# 15_-MCU_CONNECTORS.net
KiCad netlist of a schematic drawn in Altium Designer
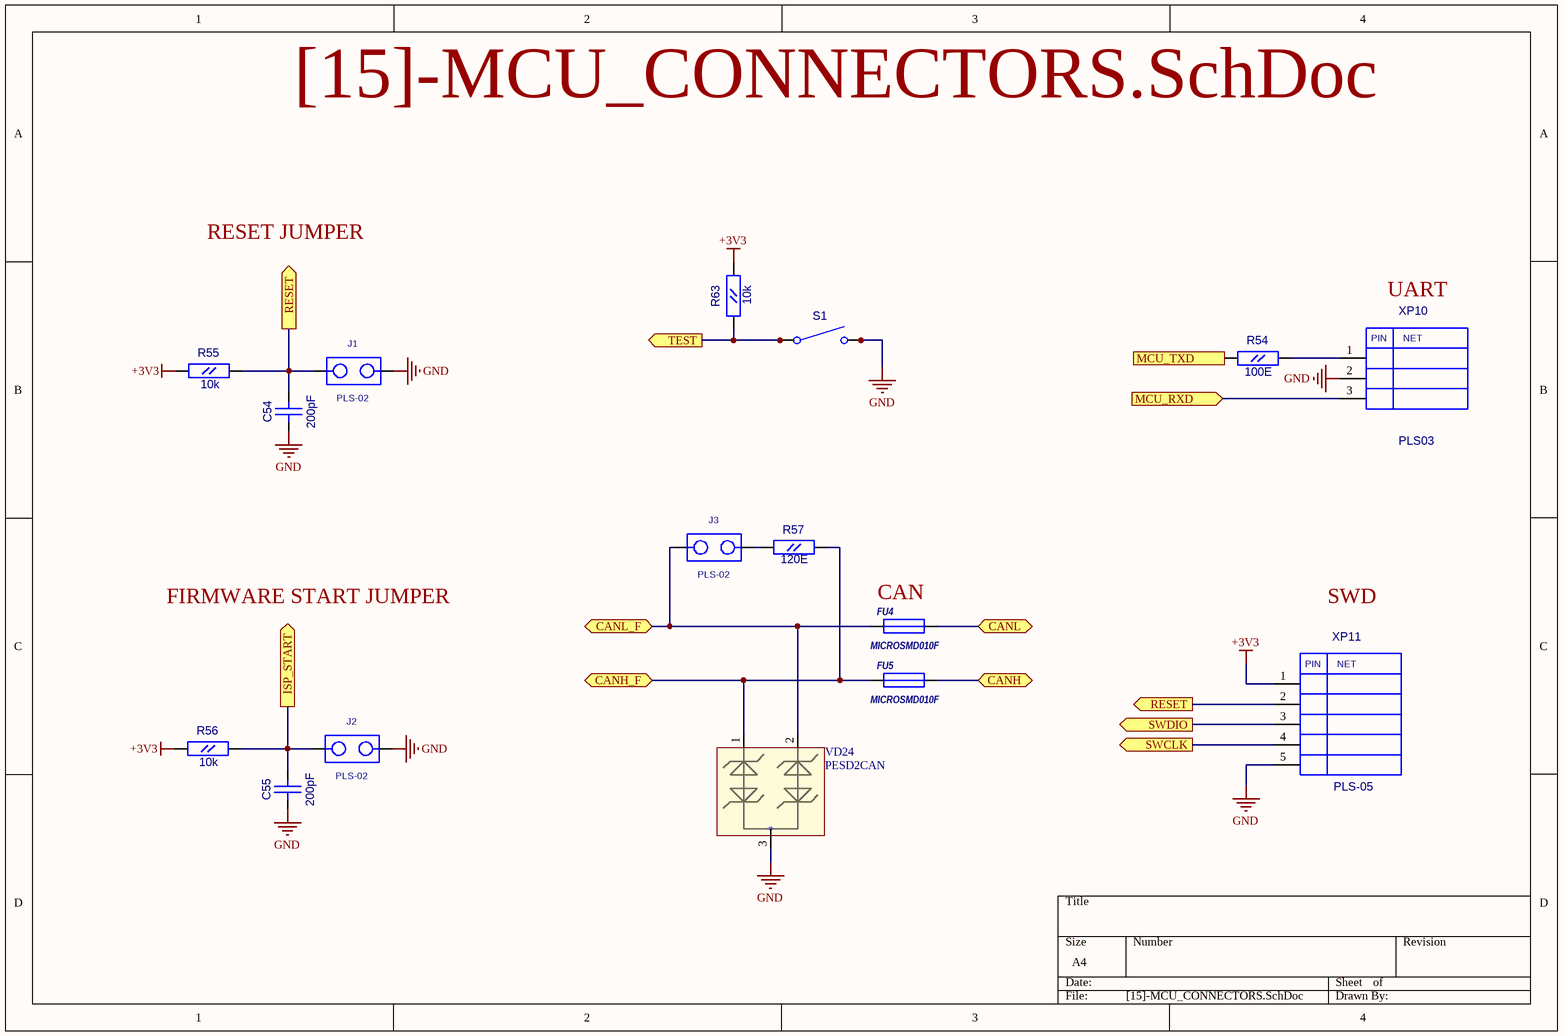
[diagram p0: [15]-MCU_CONNECTORS.SchDoc]

(export (version "E")
  (design (tool "Eeschema 10.0.6"))
  (components
    (comp (ref "C54")
      (value "200pF")
      (footprint "CC0603")
      (description "CC0603")
      (libsource (lib "gprs_modem_2") (part "CC0603"))
    )
    (comp (ref "C55")
      (value "200pF")
      (footprint "CC0603")
      (description "CC0603")
      (libsource (lib "gprs_modem_2") (part "CC0603"))
    )
    (comp (ref "FU4")
      (value "MICROSMD010F")
      (footprint "RC1210")
      (description "MICROSMD")
      (libsource (lib "gprs_modem_2") (part "MICROSMD"))
    )
    (comp (ref "FU5")
      (value "MICROSMD010F")
      (footprint "RC1210")
      (description "MICROSMD")
      (libsource (lib "gprs_modem_2") (part "MICROSMD"))
    )
    (comp (ref "J1") (value "PLS-02") (footprint "PLS-02") (libsource (lib "gprs_modem_2") (part "PLS-02")))
    (comp (ref "J2") (value "PLS-02") (footprint "PLS-02") (libsource (lib "gprs_modem_2") (part "PLS-02")))
    (comp (ref "J3") (value "PLS-02") (footprint "PLS-02") (libsource (lib "fizik_lib") (part "PLS-02")))
    (comp (ref "R54")
      (value "100E")
      (footprint "RC0603")
      (description "RC0603")
      (libsource (lib "gprs_modem_2") (part "RC0603"))
    )
    (comp (ref "R55")
      (value "10k")
      (footprint "RC0603")
      (description "RC0603")
      (libsource (lib "gprs_modem_2") (part "RC0603"))
    )
    (comp (ref "R56")
      (value "10k")
      (footprint "RC0603")
      (description "RC0603")
      (libsource (lib "gprs_modem_2") (part "RC0603"))
    )
    (comp (ref "R57")
      (value "120E")
      (footprint "RC0805")
      (description "RC0805")
      (libsource (lib "fizik_lib") (part "RC0805"))
    )
    (comp (ref "R63")
      (value "10k")
      (footprint "RC0603")
      (description "RC0603")
      (libsource (lib "fizik_lib") (part "RC0603"))
    )
    (comp (ref "S1")
      (value "DTSM-61N")
      (footprint "DTSM-61N")
      (description "Switch, Single Pole, Single Throw, Normally Open")
      (libsource (lib "fizik_lib") (part "DTSM-61N"))
    )
    (comp (ref "VD24")
      (value "PESD2CAN")
      (footprint "SOT-23(123)")
      (description "TVS for CAN")
      (libsource (lib "gprs_modem_2") (part "PESD2CAN"))
    )
    (comp (ref "XP10") (value "PLS03") (footprint "PLS-03") (libsource (lib "fizik_lib") (part "PLS03")))
    (comp (ref "XP11") (value "PLS-05") (footprint "PLS-05") (libsource (lib "gprs_modem_2") (part "PLS-05")))
  )
  (nets
    (net (code "1") (name "+3V3") (class "Default")
      (node (ref "R55") (pin "1") (pinfunction "A_1") (pintype "passive"))
      (node (ref "R56") (pin "1") (pinfunction "A_1") (pintype "passive"))
      (node (ref "R63") (pin "2") (pinfunction "B_2") (pintype "passive"))
      (node (ref "XP11") (pin "1") (pinfunction "1_1") (pintype "passive"))
    )
    (net (code "2") (name "/CANH") (class "Default") (node (ref "FU5") (pin "2") (pintype "passive")))
    (net (code "3") (name "/CANH_F") (class "Default")
      (node (ref "FU5") (pin "1") (pintype "passive"))
      (node (ref "R57") (pin "2") (pinfunction "B_2") (pintype "passive"))
      (node (ref "VD24") (pin "1") (pinfunction "1_1") (pintype "passive"))
    )
    (net (code "4") (name "/CANL") (class "Default") (node (ref "FU4") (pin "2") (pintype "passive")))
    (net (code "5") (name "/CANL_F") (class "Default")
      (node (ref "FU4") (pin "1") (pintype "passive"))
      (node (ref "J3") (pin "1") (pintype "passive"))
      (node (ref "VD24") (pin "2") (pinfunction "2_2") (pintype "passive"))
    )
    (net (code "6") (name "/ISP_START") (class "Default")
      (node (ref "C55") (pin "2") (pinfunction "B_2") (pintype "passive"))
      (node (ref "J2") (pin "1") (pintype "passive"))
      (node (ref "R56") (pin "2") (pinfunction "B_2") (pintype "passive"))
    )
    (net (code "7") (name "/MCU_RXD") (class "Default")
      (node (ref "XP10") (pin "3") (pinfunction "3_3") (pintype "passive"))
    )
    (net (code "8") (name "/MCU_TXD") (class "Default")
      (node (ref "R54") (pin "1") (pinfunction "A_1") (pintype "passive"))
    )
    (net (code "9") (name "/RESET") (class "Default")
      (node (ref "C54") (pin "2") (pinfunction "B_2") (pintype "passive"))
      (node (ref "J1") (pin "1") (pintype "passive"))
      (node (ref "R55") (pin "2") (pinfunction "B_2") (pintype "passive"))
      (node (ref "XP11") (pin "2") (pinfunction "2_2") (pintype "passive"))
    )
    (net (code "10") (name "/SWCLK") (class "Default")
      (node (ref "XP11") (pin "4") (pinfunction "4_4") (pintype "passive"))
    )
    (net (code "11") (name "/SWDIO") (class "Default")
      (node (ref "XP11") (pin "3") (pinfunction "3_3") (pintype "passive"))
    )
    (net (code "12") (name "/TEST") (class "Default")
      (node (ref "R63") (pin "1") (pinfunction "A_1") (pintype "passive"))
      (node (ref "S1") (pin "1") (pinfunction "C1_1") (pintype "passive"))
      (node (ref "S1") (pin "2") (pintype "passive"))
    )
    (net (code "13") (name "GND") (class "Default")
      (node (ref "C54") (pin "1") (pinfunction "A_1") (pintype "passive"))
      (node (ref "C55") (pin "1") (pinfunction "A_1") (pintype "passive"))
      (node (ref "J1") (pin "2") (pintype "passive"))
      (node (ref "J2") (pin "2") (pintype "passive"))
      (node (ref "S1") (pin "3") (pinfunction "C2_3") (pintype "passive"))
      (node (ref "S1") (pin "4") (pintype "passive"))
      (node (ref "VD24") (pin "3") (pinfunction "3_3") (pintype "passive"))
      (node (ref "XP10") (pin "2") (pinfunction "2_2") (pintype "passive"))
      (node (ref "XP11") (pin "5") (pinfunction "5_5") (pintype "passive"))
    )
    (net (code "14") (name "Net-(R54-B)") (class "Default")
      (node (ref "R54") (pin "2") (pinfunction "B_2") (pintype "passive"))
      (node (ref "XP10") (pin "1") (pinfunction "1_1") (pintype "passive"))
    )
    (net (code "15") (name "Net-(R57-A)") (class "Default")
      (node (ref "J3") (pin "2") (pintype "passive"))
      (node (ref "R57") (pin "1") (pinfunction "A_1") (pintype "passive"))
    )
  )
)
